# CAN_IC.net
KiCad netlist of a schematic drawn in Altium Designer
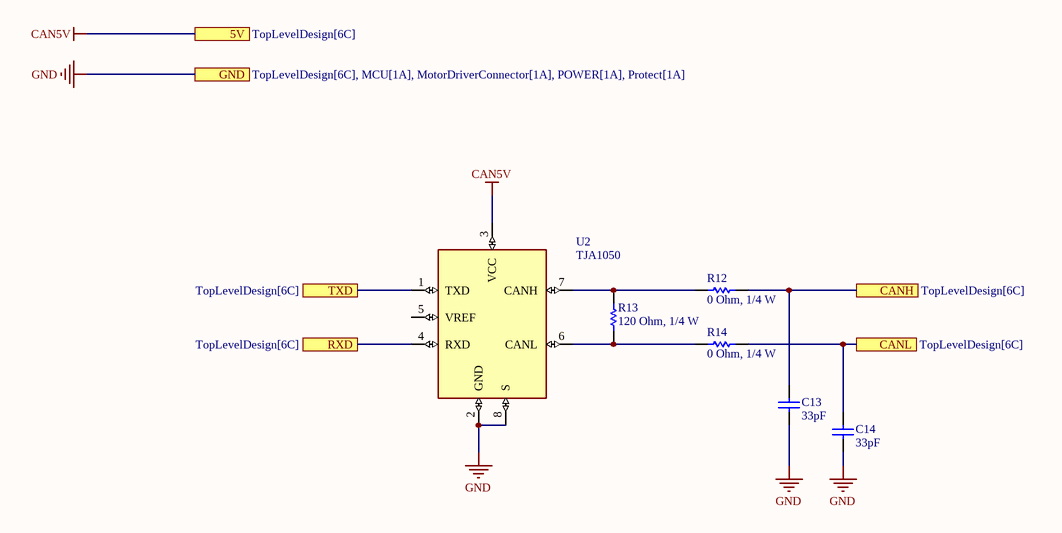
[diagram p0: CAN_IC.SchDoc]

(export (version "E")
  (design (tool "Eeschema 10.0.6"))
  (components
    (comp (ref "C13")
      (value "33pF")
      (footprint "CAP_0603")
      (description "CAP, size 0603, 33 pF, 50 VDC")
      (fields
        (field (name "TOLERANCE") "5%")
        (field (name "Comment") "0106033300550")
        (field (name "SOURCE") "Capacitor_0603_5_percent.SchLib")
      )
      (libsource (lib "Tin Tran") (part "0106036820550"))
    )
    (comp (ref "C14")
      (value "33pF")
      (footprint "CAP_0603")
      (description "CAP, size 0603, 33 pF, 50 VDC")
      (fields
        (field (name "TOLERANCE") "5%")
        (field (name "Comment") "0106033300550")
        (field (name "SOURCE") "Capacitor_0603_5_percent.SchLib")
      )
      (libsource (lib "Tin Tran") (part "0106036820550"))
    )
    (comp (ref "R12")
      (value "0 Ohm, 1/4 W")
      (footprint "resistor_0603")
      (description "RES, size 0603, 0 Ohm, 1/4 W")
      (fields (field (name "Comment") "0006030001"))
      (libsource (lib "Tin Tran") (part "00060371541"))
    )
    (comp (ref "R13")
      (value "120 Ohm, 1/4 W")
      (footprint "resistor_0603")
      (description "RES, size 0603, 120 Ohm, 1/4 W")
      (fields (field (name "Comment") "0006031211"))
      (libsource (lib "Tin Tran") (part "00060371541"))
    )
    (comp (ref "R14")
      (value "0 Ohm, 1/4 W")
      (footprint "resistor_0603")
      (description "RES, size 0603, 0 Ohm, 1/4 W")
      (fields (field (name "Comment") "0006030001"))
      (libsource (lib "Tin Tran") (part "00060371541"))
    )
    (comp (ref "U2")
      (value "TJA1050")
      (footprint "SOP8")
      (description "1/1 Transceiver Half CANbus 8-SO")
      (fields (field (name "MF") "NXP USA"))
      (libsource (lib "Tin Tran") (part "TJA1050"))
    )
  )
  (nets
    (net (code "1") (name "/CANH") (class "Default")
      (node (ref "C13") (pin "2") (pinfunction "2_2") (pintype "passive"))
      (node (ref "R12") (pin "2") (pinfunction "2_2") (pintype "passive"))
    )
    (net (code "2") (name "/CANL") (class "Default")
      (node (ref "C14") (pin "2") (pinfunction "2_2") (pintype "passive"))
      (node (ref "R14") (pin "2") (pinfunction "2_2") (pintype "passive"))
    )
    (net (code "3") (name "/RXD") (class "Default")
      (node (ref "U2") (pin "4") (pinfunction "RXD_4") (pintype "bidirectional"))
    )
    (net (code "4") (name "/TXD") (class "Default")
      (node (ref "U2") (pin "1") (pinfunction "TXD_1") (pintype "bidirectional"))
    )
    (net (code "5") (name "CAN5V") (class "Default")
      (node (ref "U2") (pin "3") (pinfunction "VCC_3") (pintype "bidirectional"))
    )
    (net (code "6") (name "GND") (class "Default")
      (node (ref "C13") (pin "1") (pinfunction "1_1") (pintype "passive"))
      (node (ref "C14") (pin "1") (pinfunction "1_1") (pintype "passive"))
      (node (ref "U2") (pin "2") (pinfunction "GND_2") (pintype "bidirectional"))
      (node (ref "U2") (pin "8") (pinfunction "S_8") (pintype "bidirectional"))
    )
    (net (code "7") (name "Net-(U2-CANH)") (class "Default")
      (node (ref "R12") (pin "1") (pinfunction "1_1") (pintype "passive"))
      (node (ref "R13") (pin "2") (pinfunction "2_2") (pintype "passive"))
      (node (ref "U2") (pin "7") (pinfunction "CANH_7") (pintype "bidirectional"))
    )
    (net (code "8") (name "Net-(U2-CANL)") (class "Default")
      (node (ref "R13") (pin "1") (pinfunction "1_1") (pintype "passive"))
      (node (ref "R14") (pin "1") (pinfunction "1_1") (pintype "passive"))
      (node (ref "U2") (pin "6") (pinfunction "CANL_6") (pintype "bidirectional"))
    )
    (net (code "9") (name "unconnected-(U2-VREF-Pad5)") (class "Default")
      (node (ref "U2") (pin "5") (pinfunction "VREF_5") (pintype "bidirectional"))
    )
  )
)
